# DistBoard.net
KiCad netlist of a schematic drawn in Altium Designer
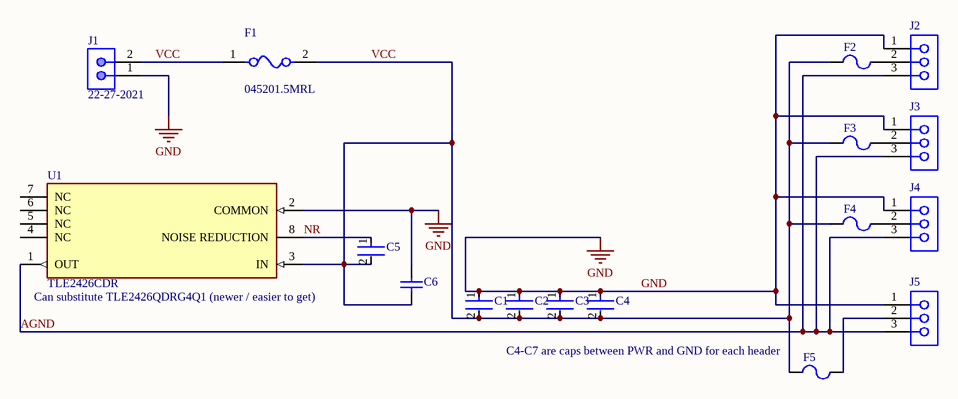
[diagram p0: DistBoard.SchDoc]

(export (version "E")
  (design (tool "Eeschema 10.0.6"))
  (components
    (comp (ref "C1")
      (value "GCJ21BR71H105KA01L")
      (footprint "FP-GCJ21B-0_3-IPC_B")
      (fields (field (name "TOLERANCE") "10%") (field (name "MANUFACTURER") "Murata"))
      (libsource (lib "Altium Content Vault") (part "02cd4be3c70576c341d710602a673aa"))
    )
    (comp (ref "C2")
      (value "GCJ21BR71H105KA01L")
      (footprint "FP-GCJ21B-0_3-IPC_B")
      (fields (field (name "TOLERANCE") "10%") (field (name "MANUFACTURER") "Murata"))
      (libsource (lib "Altium Content Vault") (part "02cd4be3c70576c341d710602a673aa"))
    )
    (comp (ref "C3")
      (value "GCJ21BR71H105KA01L")
      (footprint "FP-GCJ21B-0_3-IPC_B")
      (fields (field (name "TOLERANCE") "10%") (field (name "MANUFACTURER") "Murata"))
      (libsource (lib "Altium Content Vault") (part "02cd4be3c70576c341d710602a673aa"))
    )
    (comp (ref "C4")
      (value "GCJ21BR71H105KA01L")
      (footprint "FP-GCJ21B-0_3-IPC_B")
      (fields (field (name "TOLERANCE") "10%") (field (name "MANUFACTURER") "Murata"))
      (libsource (lib "Altium Content Vault") (part "02cd4be3c70576c341d710602a673aa"))
    )
    (comp (ref "C5")
      (value "GCD21BR71H104KA01L")
      (footprint "FP-GCD21B-0_15-IPC_C")
      (fields (field (name "TOLERANCE") "10%") (field (name "MANUFACTURER") "Murata"))
      (libsource (lib "Altium Content Vault") (part "b4654b650e69147ec39a6b967a45e02"))
    )
    (comp (ref "C6")
      (value "GRM21BR71H105KA12L")
      (footprint "CAPC2013X135X45LL10T25")
      (fields (field (name "MANUFACTURER") "Murata"))
      (libsource (lib "Altium Content Vault") (part "CAP"))
    )
    (comp (ref "F1")
      (value "045201.5MRL")
      (footprint "FP-0452-MFG")
      (description "FUSE BRD MNT 1.5A 125VAC/VDC SMD")
      (fields
        (field (name "MANUFACTURER") "Littelfuse Inc")
        (field (name "OCTOPART") "https://octopart.com/045201.5mrl-littelfuse-566412")
      )
      (libsource (lib "Altium Content Vault") (part "5bcf9b9f640e542cf0359d10258e979"))
    )
    (comp (ref "F2")
      (value "0459.250UR")
      (footprint "LFUS-459_V")
      (description "Fuse, 125 V, 250 mA, -55 to 125 degC, 2-Pin SMD, RoHS, Tape and Reel")
      (fields (field (name "MANUFACTURER") "Littelfuse"))
      (libsource (lib "Altium Content Vault") (part "FUSE-2"))
    )
    (comp (ref "F3")
      (value "0459.250UR")
      (footprint "LFUS-459_V")
      (description "Fuse, 125 V, 250 mA, -55 to 125 degC, 2-Pin SMD, RoHS, Tape and Reel")
      (fields (field (name "MANUFACTURER") "Littelfuse"))
      (libsource (lib "Altium Content Vault") (part "FUSE-2"))
    )
    (comp (ref "F4")
      (value "0459.250UR")
      (footprint "LFUS-459_V")
      (description "Fuse, 125 V, 250 mA, -55 to 125 degC, 2-Pin SMD, RoHS, Tape and Reel")
      (fields (field (name "MANUFACTURER") "Littelfuse"))
      (libsource (lib "Altium Content Vault") (part "FUSE-2"))
    )
    (comp (ref "F5")
      (value "0459.250UR")
      (footprint "LFUS-459_V")
      (description "Fuse, 125 V, 250 mA, -55 to 125 degC, 2-Pin SMD, RoHS, Tape and Reel")
      (fields (field (name "MANUFACTURER") "Littelfuse"))
      (libsource (lib "Altium Content Vault") (part "FUSE-2"))
    )
    (comp (ref "J1")
      (value "22-27-2021")
      (footprint "MOLX-22-27-2021_V")
      (fields (field (name "MANUFACTURER") "Molex") (field (name "PARTNUMBER") "0022272021"))
      (libsource (lib "Altium Content Vault") (part "CN-1P-M-R2"))
    )
    (comp (ref "J2")
      (value "SSM-103-L-SV")
      (footprint "SMTC-SSM-103-X-SV")
      (fields (field (name "MANUFACTURER") "Samtec"))
      (libsource (lib "Altium Content Vault") (part "SMTC-SSM-103-X-SV"))
    )
    (comp (ref "J3")
      (value "SSM-103-L-SV")
      (footprint "SMTC-SSM-103-X-SV")
      (fields (field (name "MANUFACTURER") "Samtec"))
      (libsource (lib "Altium Content Vault") (part "SMTC-SSM-103-X-SV"))
    )
    (comp (ref "J4")
      (value "SSM-103-L-SV")
      (footprint "SMTC-SSM-103-X-SV")
      (fields (field (name "MANUFACTURER") "Samtec"))
      (libsource (lib "Altium Content Vault") (part "SMTC-SSM-103-X-SV"))
    )
    (comp (ref "J5")
      (value "SSM-103-L-SV")
      (footprint "SMTC-SSM-103-X-SV")
      (fields (field (name "MANUFACTURER") "Samtec"))
      (libsource (lib "Altium Content Vault") (part "SMTC-SSM-103-X-SV"))
    )
    (comp (ref "U1")
      (value "TLE2426CDR")
      (footprint "FP-D0008A-IPC_B")
      (fields (field (name "TOLERANCE") "1%") (field (name "MANUFACTURER") "Texas Instruments"))
      (libsource (lib "Altium Content Vault") (part "6a05ed44ac4318f8a6b310f721958da"))
    )
  )
  (nets
    (net (code "1") (name "/AGND") (class "Default")
      (node (ref "J2") (pin "3") (pinfunction "3_3") (pintype "passive"))
      (node (ref "J3") (pin "3") (pinfunction "3_3") (pintype "passive"))
      (node (ref "J4") (pin "3") (pinfunction "3_3") (pintype "passive"))
      (node (ref "J5") (pin "3") (pinfunction "3_3") (pintype "passive"))
      (node (ref "U1") (pin "1") (pinfunction "OUT_1") (pintype "output"))
    )
    (net (code "2") (name "/NR") (class "Default")
      (node (ref "C5") (pin "1") (pinfunction "1_1") (pintype "passive"))
      (node (ref "U1") (pin "8") (pinfunction "NOISE_REDUCTION_8") (pintype "passive"))
    )
    (net (code "3") (name "/VCC") (class "Default")
      (node (ref "C1") (pin "2") (pinfunction "2_2") (pintype "passive"))
      (node (ref "C2") (pin "2") (pinfunction "2_2") (pintype "passive"))
      (node (ref "C3") (pin "2") (pinfunction "2_2") (pintype "passive"))
      (node (ref "C4") (pin "2") (pinfunction "2_2") (pintype "passive"))
      (node (ref "C5") (pin "2") (pinfunction "2_2") (pintype "passive"))
      (node (ref "C6") (pin "1") (pinfunction "1_1") (pintype "passive"))
      (node (ref "F1") (pin "1") (pinfunction "1_1") (pintype "passive"))
      (node (ref "F1") (pin "2") (pinfunction "2_2") (pintype "passive"))
      (node (ref "F2") (pin "1") (pinfunction "1_1") (pintype "passive"))
      (node (ref "F3") (pin "1") (pinfunction "1_1") (pintype "passive"))
      (node (ref "F4") (pin "1") (pinfunction "1_1") (pintype "passive"))
      (node (ref "F5") (pin "1") (pinfunction "1_1") (pintype "passive"))
      (node (ref "J1") (pin "2") (pinfunction "2_2") (pintype "passive"))
      (node (ref "U1") (pin "3") (pinfunction "IN_3") (pintype "input"))
    )
    (net (code "4") (name "GND") (class "Default")
      (node (ref "C1") (pin "1") (pinfunction "1_1") (pintype "passive"))
      (node (ref "C2") (pin "1") (pinfunction "1_1") (pintype "passive"))
      (node (ref "C3") (pin "1") (pinfunction "1_1") (pintype "passive"))
      (node (ref "C4") (pin "1") (pinfunction "1_1") (pintype "passive"))
      (node (ref "C6") (pin "2") (pinfunction "2_2") (pintype "passive"))
      (node (ref "J1") (pin "1") (pinfunction "1_1") (pintype "passive"))
      (node (ref "J2") (pin "1") (pinfunction "1_1") (pintype "passive"))
      (node (ref "J3") (pin "1") (pinfunction "1_1") (pintype "passive"))
      (node (ref "J4") (pin "1") (pinfunction "1_1") (pintype "passive"))
      (node (ref "J5") (pin "1") (pinfunction "1_1") (pintype "passive"))
      (node (ref "U1") (pin "2") (pinfunction "COMMON_2") (pintype "input"))
    )
    (net (code "5") (name "Net-(F2-Pad2)") (class "Default")
      (node (ref "F2") (pin "2") (pinfunction "2_2") (pintype "passive"))
      (node (ref "J2") (pin "2") (pinfunction "2_2") (pintype "passive"))
    )
    (net (code "6") (name "Net-(F3-Pad2)") (class "Default")
      (node (ref "F3") (pin "2") (pinfunction "2_2") (pintype "passive"))
      (node (ref "J3") (pin "2") (pinfunction "2_2") (pintype "passive"))
    )
    (net (code "7") (name "Net-(F4-Pad2)") (class "Default")
      (node (ref "F4") (pin "2") (pinfunction "2_2") (pintype "passive"))
      (node (ref "J4") (pin "2") (pinfunction "2_2") (pintype "passive"))
    )
    (net (code "8") (name "Net-(F5-Pad2)") (class "Default")
      (node (ref "F5") (pin "2") (pinfunction "2_2") (pintype "passive"))
      (node (ref "J5") (pin "2") (pinfunction "2_2") (pintype "passive"))
    )
    (net (code "9") (name "unconnected-(U1-NC-Pad4)") (class "Default")
      (node (ref "U1") (pin "4") (pinfunction "NC_4") (pintype "passive"))
    )
    (net (code "10") (name "unconnected-(U1-NC-Pad5)") (class "Default")
      (node (ref "U1") (pin "5") (pinfunction "NC_5") (pintype "passive"))
    )
    (net (code "11") (name "unconnected-(U1-NC-Pad6)") (class "Default")
      (node (ref "U1") (pin "6") (pinfunction "NC_6") (pintype "passive"))
    )
    (net (code "12") (name "unconnected-(U1-NC-Pad7)") (class "Default")
      (node (ref "U1") (pin "7") (pinfunction "NC_7") (pintype "passive"))
    )
  )
)
